# HDR_camera_controller.net
KiCad netlist of a schematic drawn in EAGLE
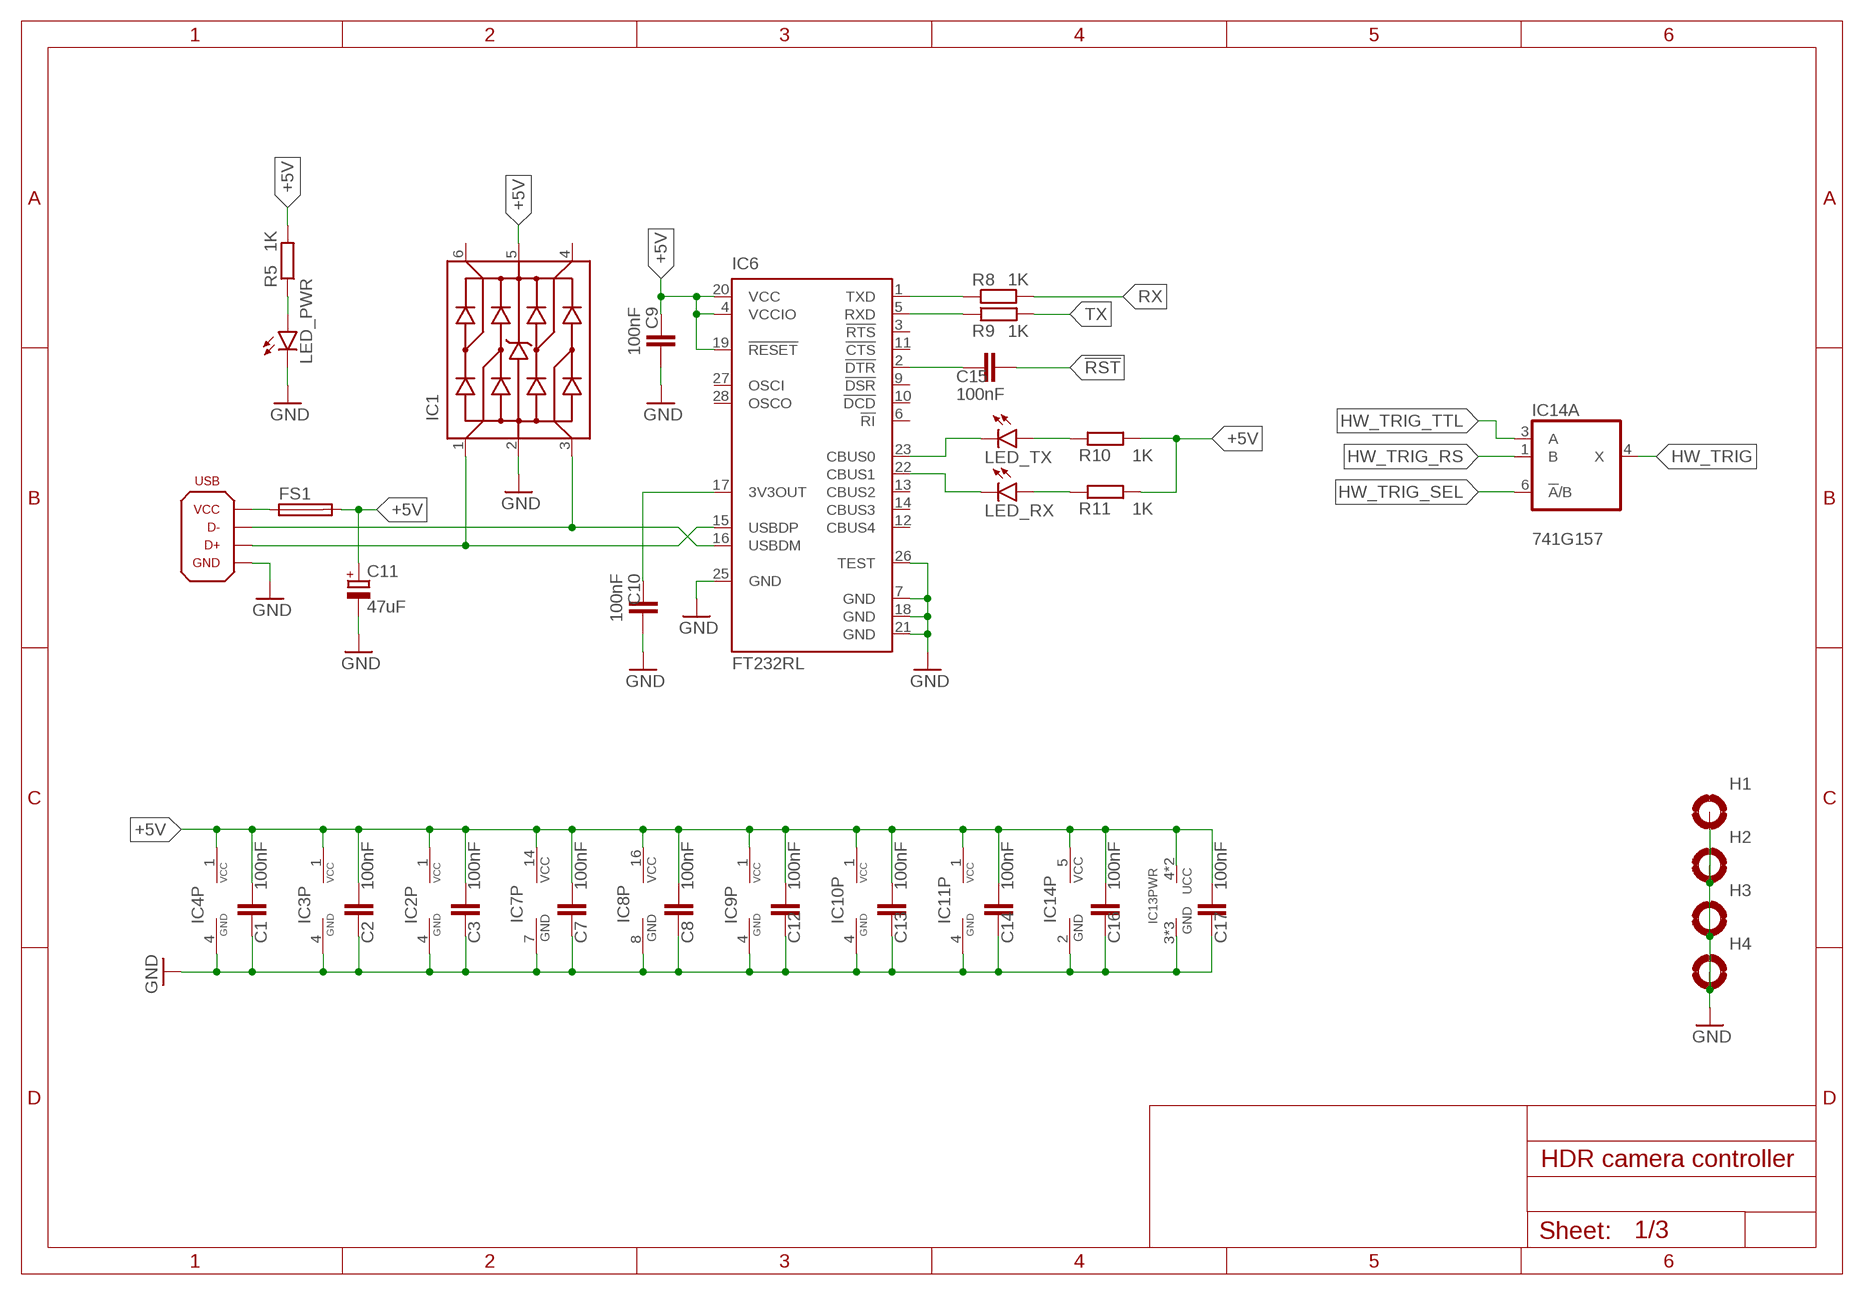
[diagram p0: schematic, sheet 1]
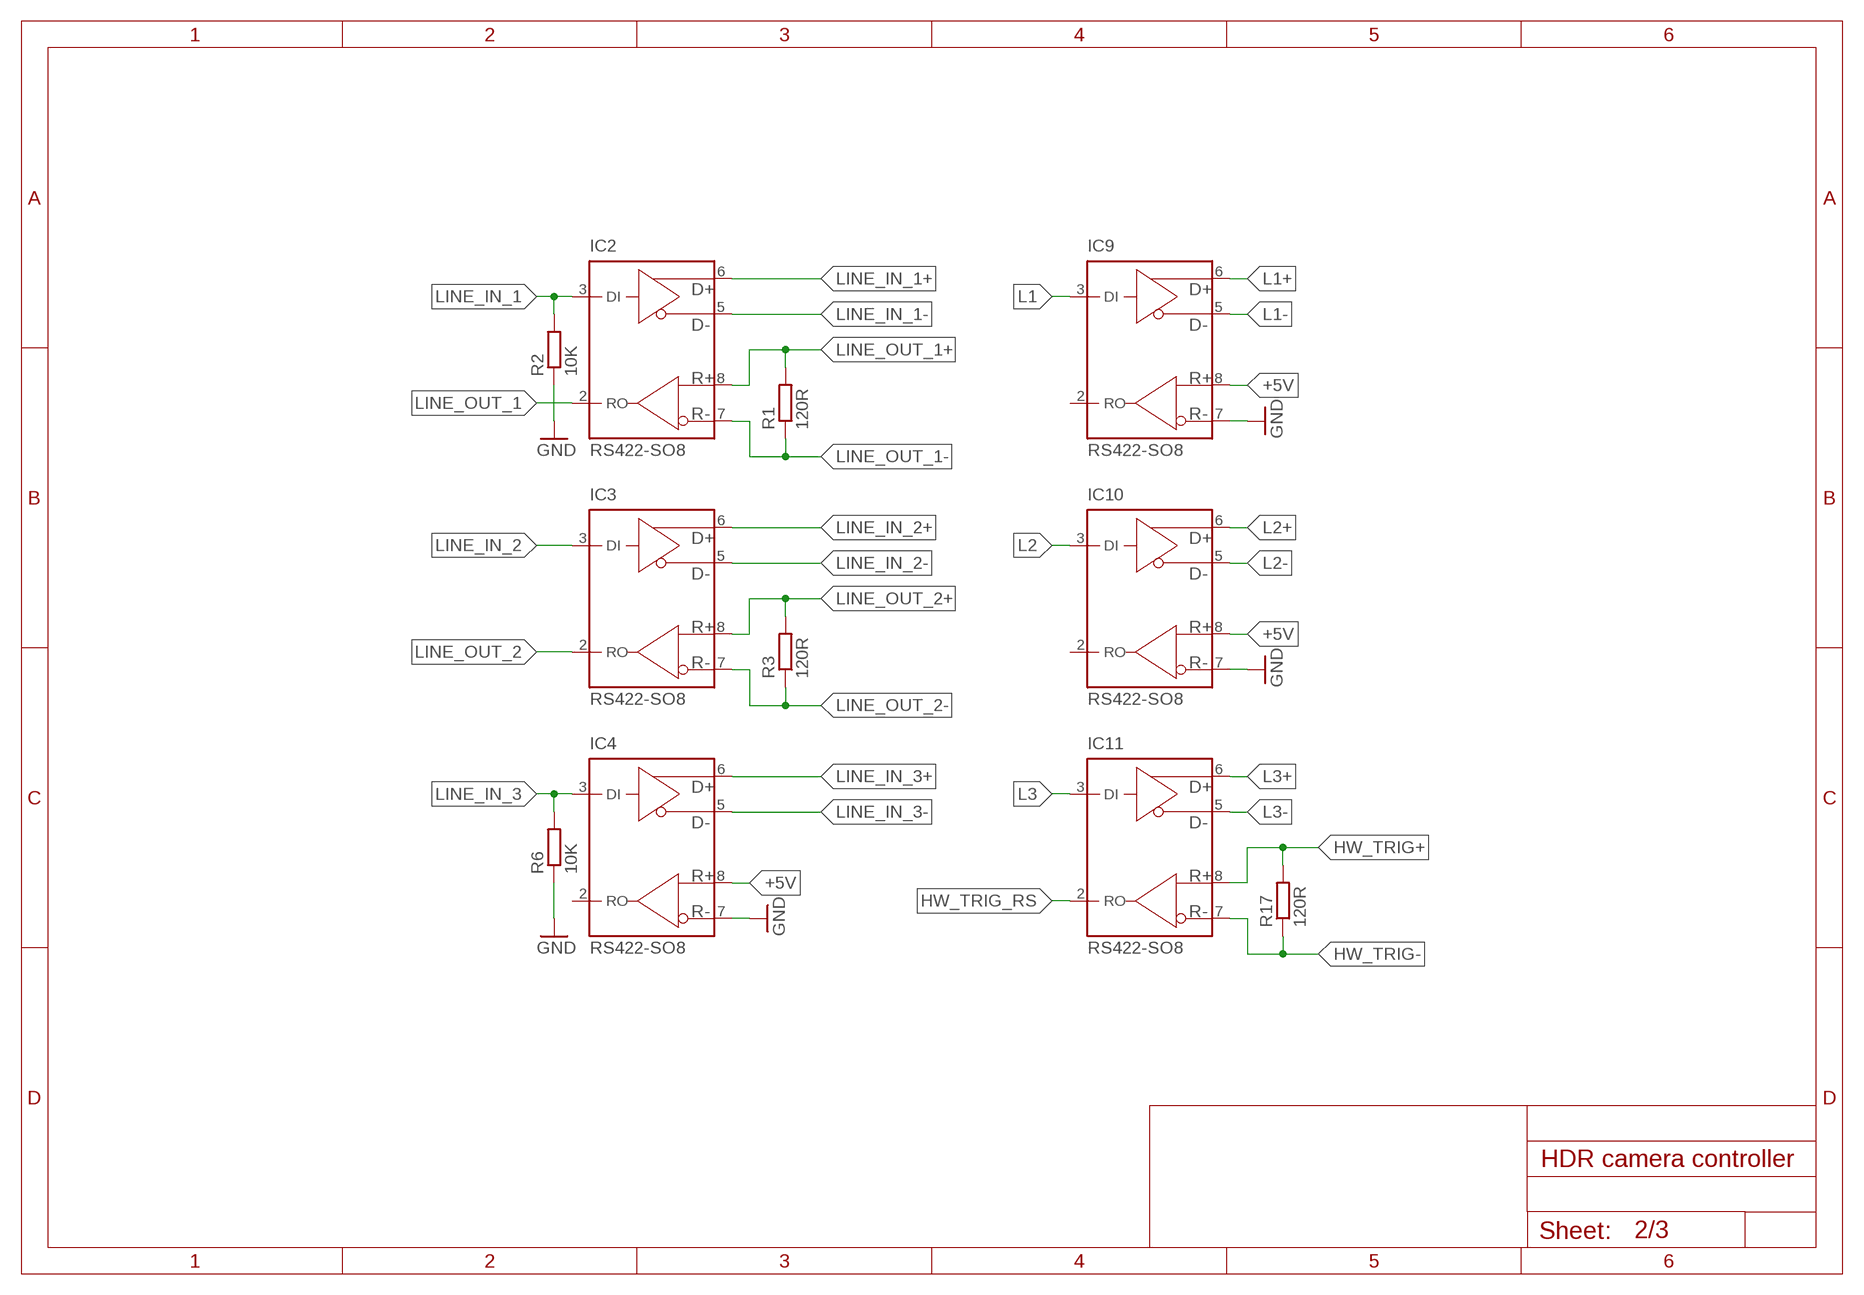
[diagram p1: schematic, sheet 2]
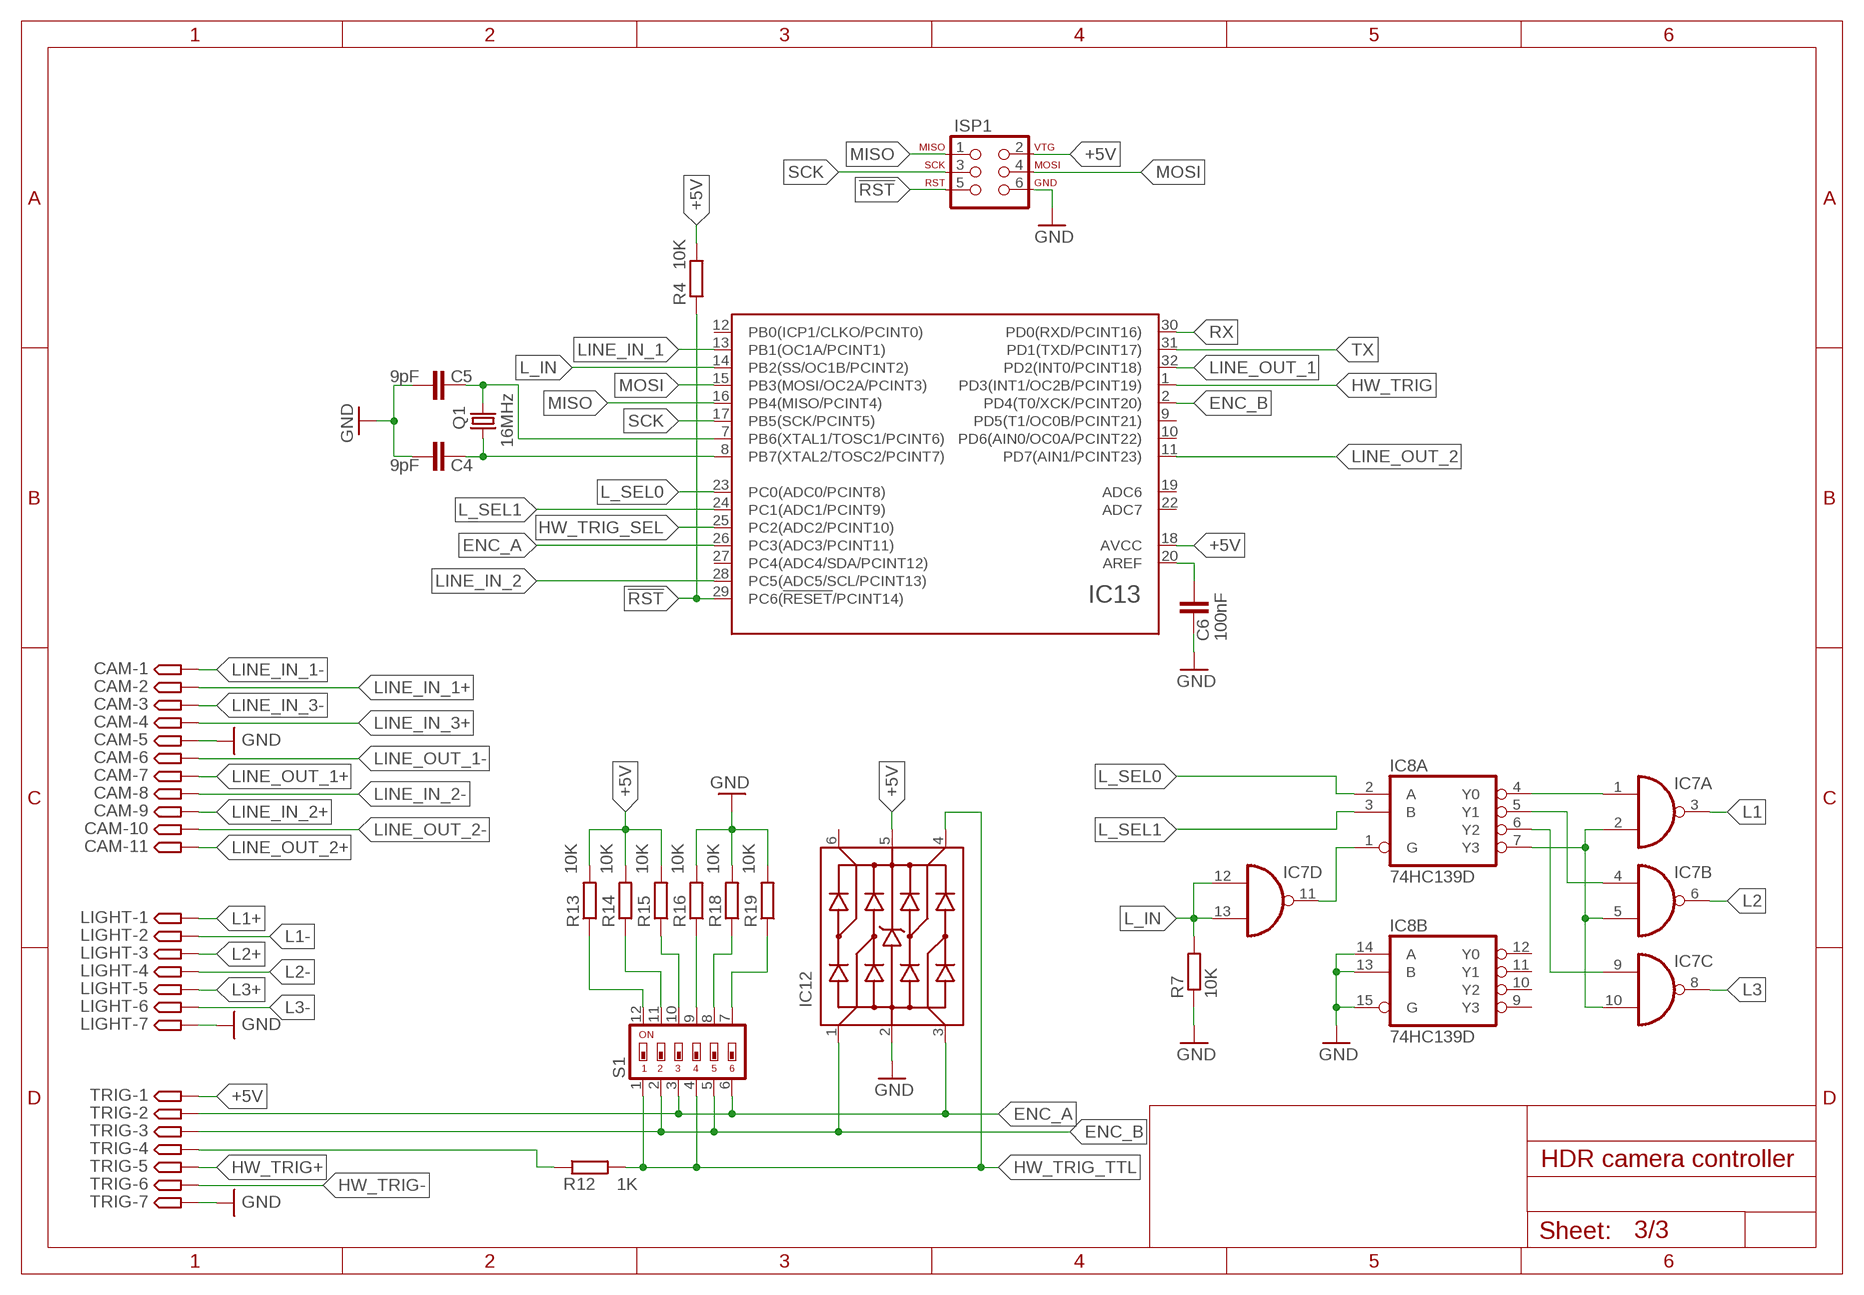
[diagram p2: schematic, sheet 3]

(export (version "E")
  (design (tool "Eeschema 10.0.6"))
  (components
    (comp (ref "C1")
      (value "100nF")
      (footprint "eagle-import:C0805")
      (libsource (lib "eagle-import") (part "C-EUC0805"))
    )
    (comp (ref "C2")
      (value "100nF")
      (footprint "eagle-import:C0805")
      (libsource (lib "eagle-import") (part "C-EUC0805"))
    )
    (comp (ref "C3")
      (value "100nF")
      (footprint "eagle-import:C0805")
      (libsource (lib "eagle-import") (part "C-EUC0805"))
    )
    (comp (ref "C7")
      (value "100nF")
      (footprint "eagle-import:C0805")
      (libsource (lib "eagle-import") (part "C-EUC0805"))
    )
    (comp (ref "C8")
      (value "100nF")
      (footprint "eagle-import:C0805")
      (libsource (lib "eagle-import") (part "C-EUC0805"))
    )
    (comp (ref "C9")
      (value "100nF")
      (footprint "eagle-import:C0805")
      (libsource (lib "eagle-import") (part "C-EUC0805"))
    )
    (comp (ref "C10")
      (value "100nF")
      (footprint "eagle-import:C0805")
      (libsource (lib "eagle-import") (part "C-EUC0805"))
    )
    (comp (ref "C11")
      (value "47uF")
      (footprint "eagle-import:153CLV-0605")
      (fields (field (name "MPN") "SC1E476M6L005VR"))
      (libsource (lib "eagle-import") (part "CPOL-EU153CLV-0605"))
    )
    (comp (ref "C12")
      (value "100nF")
      (footprint "eagle-import:C0805")
      (libsource (lib "eagle-import") (part "C-EUC0805"))
    )
    (comp (ref "C13")
      (value "100nF")
      (footprint "eagle-import:C0805")
      (libsource (lib "eagle-import") (part "C-EUC0805"))
    )
    (comp (ref "C14")
      (value "100nF")
      (footprint "eagle-import:C0805")
      (libsource (lib "eagle-import") (part "C-EUC0805"))
    )
    (comp (ref "C15")
      (value "100nF")
      (footprint "eagle-import:C0805")
      (libsource (lib "eagle-import") (part "C-EUC0805"))
    )
    (comp (ref "C16")
      (value "100nF")
      (footprint "eagle-import:C0805")
      (libsource (lib "eagle-import") (part "C-EUC0805"))
    )
    (comp (ref "C17")
      (value "100nF")
      (footprint "eagle-import:C0805")
      (libsource (lib "eagle-import") (part "C-EUC0805"))
    )
    (comp (ref "FS1")
      (value "POLYFUSE_1210")
      (footprint "eagle-import:1210")
      (fields (field (name "MPN") "SM010-60"))
      (libsource (lib "eagle-import") (part "POLYFUSE_1210"))
    )
    (comp (ref "H1")
      (value "HOLE-3MM_PLATED")
      (footprint "eagle-import:3MM_PLATED")
      (libsource (lib "eagle-import") (part "HOLE-3MM_PLATED"))
    )
    (comp (ref "H2")
      (value "HOLE-3MM_PLATED")
      (footprint "eagle-import:3MM_PLATED")
      (libsource (lib "eagle-import") (part "HOLE-3MM_PLATED"))
    )
    (comp (ref "H3")
      (value "HOLE-3MM_PLATED")
      (footprint "eagle-import:3MM_PLATED")
      (libsource (lib "eagle-import") (part "HOLE-3MM_PLATED"))
    )
    (comp (ref "H4")
      (value "HOLE-3MM_PLATED")
      (footprint "eagle-import:3MM_PLATED")
      (libsource (lib "eagle-import") (part "HOLE-3MM_PLATED"))
    )
    (comp (ref "IC1")
      (value "USBLC6-4")
      (footprint "eagle-import:SOT23-6")
      (fields (field (name "MPN") "USBLC6"))
      (libsource (lib "eagle-import") (part "USBLC6-4"))
    )
    (comp (ref "IC2")
      (value "RS422-SO8")
      (footprint "eagle-import:SO08")
      (fields
        (field (name "MF") "MAXIM")
        (field (name "MPN") "MAX488CSA")
        (field (name "MPN_1") "DS8921AMX/NOPB")
      )
      (libsource (lib "eagle-import") (part "RS422-SO8"))
    )
    (comp (ref "IC3")
      (value "RS422-SO8")
      (footprint "eagle-import:SO08")
      (fields
        (field (name "MF") "MAXIM")
        (field (name "MPN") "MAX488CSA")
        (field (name "MPN_1") "DS8921AMX/NOPB")
      )
      (libsource (lib "eagle-import") (part "RS422-SO8"))
    )
    (comp (ref "IC4")
      (value "RS422-SO8")
      (footprint "eagle-import:SO08")
      (fields
        (field (name "MF") "MAXIM")
        (field (name "MPN") "MAX488CSA")
        (field (name "MPN_1") "DS8921AMX/NOPB")
      )
      (libsource (lib "eagle-import") (part "RS422-SO8"))
    )
    (comp (ref "IC6")
      (value "FT232RL")
      (footprint "eagle-import:SSOP28")
      (libsource (lib "eagle-import") (part "FT232RL"))
    )
    (comp (ref "IC7")
      (value "74HC00D")
      (footprint "eagle-import:SO14")
      (fields (field (name "MPN") "SN74HC00DR"))
      (libsource (lib "eagle-import") (part "7400DHC"))
    )
    (comp (ref "IC8")
      (value "74HC139D")
      (footprint "eagle-import:SO16")
      (fields (field (name "MPN") "SN74HC139DR"))
      (libsource (lib "eagle-import") (part "74139DHC"))
    )
    (comp (ref "IC9")
      (value "RS422-SO8")
      (footprint "eagle-import:SO08")
      (fields
        (field (name "MF") "MAXIM")
        (field (name "MPN") "MAX488CSA")
        (field (name "MPN_1") "DS8921AMX/NOPB")
      )
      (libsource (lib "eagle-import") (part "RS422-SO8"))
    )
    (comp (ref "IC10")
      (value "RS422-SO8")
      (footprint "eagle-import:SO08")
      (fields
        (field (name "MF") "MAXIM")
        (field (name "MPN") "MAX488CSA")
        (field (name "MPN_1") "DS8921AMX/NOPB")
      )
      (libsource (lib "eagle-import") (part "RS422-SO8"))
    )
    (comp (ref "IC11")
      (value "RS422-SO8")
      (footprint "eagle-import:SO08")
      (fields
        (field (name "MF") "MAXIM")
        (field (name "MPN") "MAX488CSA")
        (field (name "MPN_1") "DS8921AMX/NOPB")
      )
      (libsource (lib "eagle-import") (part "RS422-SO8"))
    )
    (comp (ref "IC13")
      (value "ATMEGA48/88/168/328-AU")
      (footprint "eagle-import:TQFP32-08")
      (libsource (lib "eagle-import") (part "ATMEGA48/88/168/328-AU"))
    )
    (comp (ref "IC14")
      (value "741G157")
      (footprint "eagle-import:SOT457W_PHILIPS")
      (fields (field (name "MPN") "74LVC1G157GV.125"))
      (libsource (lib "eagle-import") (part "741G157"))
    )
    (comp (ref "LED_PWR")
      (value "LEDSML0805")
      (footprint "eagle-import:SML0805")
      (libsource (lib "eagle-import") (part "LEDSML0805"))
    )
    (comp (ref "LED_RX")
      (value "LEDSML0805")
      (footprint "eagle-import:SML0805")
      (libsource (lib "eagle-import") (part "LEDSML0805"))
    )
    (comp (ref "LED_TX")
      (value "LEDSML0805")
      (footprint "eagle-import:SML0805")
      (libsource (lib "eagle-import") (part "LEDSML0805"))
    )
    (comp (ref "R5")
      (value "1K")
      (footprint "eagle-import:R0805")
      (libsource (lib "eagle-import") (part "R-EU_R0805"))
    )
    (comp (ref "R8")
      (value "1K")
      (footprint "eagle-import:R0805")
      (libsource (lib "eagle-import") (part "R-EU_R0805"))
    )
    (comp (ref "R9")
      (value "1K")
      (footprint "eagle-import:R0805")
      (libsource (lib "eagle-import") (part "R-EU_R0805"))
    )
    (comp (ref "R10")
      (value "1K")
      (footprint "eagle-import:R0805")
      (libsource (lib "eagle-import") (part "R-EU_R0805"))
    )
    (comp (ref "R11")
      (value "1K")
      (footprint "eagle-import:R0805")
      (libsource (lib "eagle-import") (part "R-EU_R0805"))
    )
    (comp (ref "USB")
      (value "USB_AB-B_SMD")
      (footprint "eagle-import:USB_B_SMD")
      (fields (field (name "MPN") "USBB-G-SMD"))
      (libsource (lib "eagle-import") (part "USB_AB-B_SMD"))
    )
    (comp (ref "C4")
      (value "9pF")
      (footprint "eagle-import:C0805")
      (libsource (lib "eagle-import") (part "C-EUC0805"))
    )
    (comp (ref "C5")
      (value "9pF")
      (footprint "eagle-import:C0805")
      (libsource (lib "eagle-import") (part "C-EUC0805"))
    )
    (comp (ref "C6")
      (value "100nF")
      (footprint "eagle-import:C0805")
      (libsource (lib "eagle-import") (part "C-EUC0805"))
    )
    (comp (ref "CAM")
      (value "SMPAD-11")
      (footprint "eagle-import:S-11P")
      (libsource (lib "eagle-import") (part "SMPAD-11"))
    )
    (comp (ref "IC12")
      (value "USBLC6-4")
      (footprint "eagle-import:SOT23-6")
      (fields (field (name "MPN") "USBLC6"))
      (libsource (lib "eagle-import") (part "USBLC6-4"))
    )
    (comp (ref "ISP1")
      (value "ISP-SMD")
      (footprint "eagle-import:ISP_SMD")
      (libsource (lib "eagle-import") (part "ISP-SMD"))
    )
    (comp (ref "LIGHT")
      (value "SMPAD-7")
      (footprint "eagle-import:S-7P")
      (libsource (lib "eagle-import") (part "SMPAD-7"))
    )
    (comp (ref "Q1")
      (value "16MHz")
      (footprint "eagle-import:CRYSTAL-3.2X2.5")
      (fields (field (name "MPN") "3225-16M-SR"))
      (libsource (lib "eagle-import") (part "RESONATOR_CRY"))
    )
    (comp (ref "R4")
      (value "10K")
      (footprint "eagle-import:R0805")
      (libsource (lib "eagle-import") (part "R-EU_R0805"))
    )
    (comp (ref "R7")
      (value "10K")
      (footprint "eagle-import:R0805")
      (libsource (lib "eagle-import") (part "R-EU_R0805"))
    )
    (comp (ref "R12")
      (value "1K")
      (footprint "eagle-import:R0805")
      (libsource (lib "eagle-import") (part "R-EU_R0805"))
    )
    (comp (ref "R13")
      (value "10K")
      (footprint "eagle-import:R0805")
      (libsource (lib "eagle-import") (part "R-EU_R0805"))
    )
    (comp (ref "R14")
      (value "10K")
      (footprint "eagle-import:R0805")
      (libsource (lib "eagle-import") (part "R-EU_R0805"))
    )
    (comp (ref "R15")
      (value "10K")
      (footprint "eagle-import:R0805")
      (libsource (lib "eagle-import") (part "R-EU_R0805"))
    )
    (comp (ref "R16")
      (value "10K")
      (footprint "eagle-import:R0805")
      (libsource (lib "eagle-import") (part "R-EU_R0805"))
    )
    (comp (ref "R18")
      (value "10K")
      (footprint "eagle-import:R0805")
      (libsource (lib "eagle-import") (part "R-EU_R0805"))
    )
    (comp (ref "R19")
      (value "10K")
      (footprint "eagle-import:R0805")
      (libsource (lib "eagle-import") (part "R-EU_R0805"))
    )
    (comp (ref "S1")
      (value "SWS006")
      (footprint "eagle-import:SMS-006")
      (fields (field (name "MPN") "A6S-6102-H"))
      (libsource (lib "eagle-import") (part "SWS006"))
    )
    (comp (ref "TRIG")
      (value "SMPAD-7")
      (footprint "eagle-import:S-7P")
      (libsource (lib "eagle-import") (part "SMPAD-7"))
    )
    (comp (ref "R1")
      (value "120R")
      (footprint "eagle-import:R0805")
      (libsource (lib "eagle-import") (part "R-EU_R0805"))
    )
    (comp (ref "R2")
      (value "10K")
      (footprint "eagle-import:R0805")
      (libsource (lib "eagle-import") (part "R-EU_R0805"))
    )
    (comp (ref "R3")
      (value "120R")
      (footprint "eagle-import:R0805")
      (libsource (lib "eagle-import") (part "R-EU_R0805"))
    )
    (comp (ref "R6")
      (value "10K")
      (footprint "eagle-import:R0805")
      (libsource (lib "eagle-import") (part "R-EU_R0805"))
    )
    (comp (ref "R17")
      (value "120R")
      (footprint "eagle-import:R0805")
      (libsource (lib "eagle-import") (part "R-EU_R0805"))
    )
  )
  (nets
    (net (code "1") (name "+5V") (class "Default")
      (node (ref "C1") (pin "1") (pinfunction "1_1") (pintype "passive"))
      (node (ref "C11") (pin "+") (pinfunction "+_+") (pintype "passive"))
      (node (ref "C12") (pin "1") (pinfunction "1_1") (pintype "passive"))
      (node (ref "C13") (pin "1") (pinfunction "1_1") (pintype "passive"))
      (node (ref "C14") (pin "1") (pinfunction "1_1") (pintype "passive"))
      (node (ref "C16") (pin "1") (pinfunction "1_1") (pintype "passive"))
      (node (ref "C17") (pin "1") (pinfunction "1_1") (pintype "passive"))
      (node (ref "C2") (pin "1") (pinfunction "1_1") (pintype "passive"))
      (node (ref "C3") (pin "1") (pinfunction "1_1") (pintype "passive"))
      (node (ref "C7") (pin "1") (pinfunction "1_1") (pintype "passive"))
      (node (ref "C8") (pin "1") (pinfunction "1_1") (pintype "passive"))
      (node (ref "C9") (pin "2") (pinfunction "2_2") (pintype "passive"))
      (node (ref "FS1") (pin "2") (pinfunction "2_2") (pintype "passive"))
      (node (ref "IC1") (pin "5") (pinfunction "P$5_5") (pintype "bidirectional"))
      (node (ref "IC10") (pin "1") (pinfunction "VCC_1") (pintype "power_in"))
      (node (ref "IC10") (pin "8") (pinfunction "R+_8") (pintype "input"))
      (node (ref "IC11") (pin "1") (pinfunction "VCC_1") (pintype "power_in"))
      (node (ref "IC12") (pin "5") (pinfunction "P$5_5") (pintype "bidirectional"))
      (node (ref "IC13") (pin "18") (pinfunction "AVCC_18") (pintype "power_in"))
      (node (ref "IC13") (pin "4") (pinfunction "UCC_4") (pintype "power_in"))
      (node (ref "IC13") (pin "6") (pinfunction "UCC_6") (pintype "power_in"))
      (node (ref "IC14") (pin "5") (pinfunction "VCC_5") (pintype "power_in"))
      (node (ref "IC2") (pin "1") (pinfunction "VCC_1") (pintype "power_in"))
      (node (ref "IC3") (pin "1") (pinfunction "VCC_1") (pintype "power_in"))
      (node (ref "IC4") (pin "1") (pinfunction "VCC_1") (pintype "power_in"))
      (node (ref "IC4") (pin "8") (pinfunction "R+_8") (pintype "input"))
      (node (ref "IC6") (pin "19") (pinfunction "~{RESET}_19") (pintype "input"))
      (node (ref "IC6") (pin "20") (pinfunction "VCC_20") (pintype "power_in"))
      (node (ref "IC6") (pin "4") (pinfunction "VCCIO_4") (pintype "power_in"))
      (node (ref "IC7") (pin "14") (pinfunction "VCC_14") (pintype "power_in"))
      (node (ref "IC8") (pin "16") (pinfunction "VCC_16") (pintype "power_in"))
      (node (ref "IC9") (pin "1") (pinfunction "VCC_1") (pintype "power_in"))
      (node (ref "IC9") (pin "8") (pinfunction "R+_8") (pintype "input"))
      (node (ref "ISP1") (pin "2") (pinfunction "VTG_2") (pintype "passive"))
      (node (ref "R10") (pin "2") (pinfunction "2_2") (pintype "passive"))
      (node (ref "R11") (pin "2") (pinfunction "2_2") (pintype "passive"))
      (node (ref "R13") (pin "2") (pinfunction "2_2") (pintype "passive"))
      (node (ref "R14") (pin "2") (pinfunction "2_2") (pintype "passive"))
      (node (ref "R15") (pin "2") (pinfunction "2_2") (pintype "passive"))
      (node (ref "R4") (pin "2") (pinfunction "2_2") (pintype "passive"))
      (node (ref "R5") (pin "2") (pinfunction "2_2") (pintype "passive"))
      (node (ref "TRIG") (pin "1") (pinfunction "P_1") (pintype "passive"))
    )
    (net (code "2") (name "ENC_A") (class "Default")
      (node (ref "IC12") (pin "3") (pinfunction "P$3_3") (pintype "bidirectional"))
      (node (ref "IC13") (pin "26") (pinfunction "PC3(ADC3/PCINT11)_26") (pintype "bidirectional"))
      (node (ref "S1") (pin "3") (pinfunction "3_3") (pintype "passive"))
      (node (ref "S1") (pin "6") (pinfunction "6_6") (pintype "passive"))
      (node (ref "TRIG") (pin "2") (pinfunction "P_2") (pintype "passive"))
    )
    (net (code "3") (name "ENC_B") (class "Default")
      (node (ref "IC12") (pin "1") (pinfunction "P$1_1") (pintype "bidirectional"))
      (node (ref "IC13") (pin "2") (pinfunction "PD4(T0/XCK/PCINT20)_2") (pintype "bidirectional"))
      (node (ref "S1") (pin "2") (pinfunction "2_2") (pintype "passive"))
      (node (ref "S1") (pin "5") (pinfunction "5_5") (pintype "passive"))
      (node (ref "TRIG") (pin "3") (pinfunction "P_3") (pintype "passive"))
    )
    (net (code "4") (name "GND") (class "Default")
      (node (ref "C1") (pin "2") (pinfunction "2_2") (pintype "passive"))
      (node (ref "C10") (pin "1") (pinfunction "1_1") (pintype "passive"))
      (node (ref "C11") (pin "-") (pinfunction "-_-") (pintype "passive"))
      (node (ref "C12") (pin "2") (pinfunction "2_2") (pintype "passive"))
      (node (ref "C13") (pin "2") (pinfunction "2_2") (pintype "passive"))
      (node (ref "C14") (pin "2") (pinfunction "2_2") (pintype "passive"))
      (node (ref "C16") (pin "2") (pinfunction "2_2") (pintype "passive"))
      (node (ref "C17") (pin "2") (pinfunction "2_2") (pintype "passive"))
      (node (ref "C2") (pin "2") (pinfunction "2_2") (pintype "passive"))
      (node (ref "C3") (pin "2") (pinfunction "2_2") (pintype "passive"))
      (node (ref "C4") (pin "1") (pinfunction "1_1") (pintype "passive"))
      (node (ref "C5") (pin "1") (pinfunction "1_1") (pintype "passive"))
      (node (ref "C6") (pin "2") (pinfunction "2_2") (pintype "passive"))
      (node (ref "C7") (pin "2") (pinfunction "2_2") (pintype "passive"))
      (node (ref "C8") (pin "2") (pinfunction "2_2") (pintype "passive"))
      (node (ref "C9") (pin "1") (pinfunction "1_1") (pintype "passive"))
      (node (ref "CAM") (pin "5") (pinfunction "P_5") (pintype "passive"))
      (node (ref "H1") (pin "1") (pinfunction "MOUNT_1") (pintype "passive"))
      (node (ref "H2") (pin "1") (pinfunction "MOUNT_1") (pintype "passive"))
      (node (ref "H3") (pin "1") (pinfunction "MOUNT_1") (pintype "passive"))
      (node (ref "H4") (pin "1") (pinfunction "MOUNT_1") (pintype "passive"))
      (node (ref "IC1") (pin "2") (pinfunction "P$2_2") (pintype "bidirectional"))
      (node (ref "IC10") (pin "4") (pinfunction "GND_4") (pintype "power_in"))
      (node (ref "IC10") (pin "7") (pinfunction "R-_7") (pintype "input"))
      (node (ref "IC11") (pin "4") (pinfunction "GND_4") (pintype "power_in"))
      (node (ref "IC12") (pin "2") (pinfunction "P$2_2") (pintype "bidirectional"))
      (node (ref "IC13") (pin "21") (pinfunction "GND_21") (pintype "power_in"))
      (node (ref "IC13") (pin "3") (pinfunction "GND_3") (pintype "power_in"))
      (node (ref "IC13") (pin "5") (pinfunction "GND_5") (pintype "power_in"))
      (node (ref "IC14") (pin "2") (pinfunction "GND_2") (pintype "power_in"))
      (node (ref "IC2") (pin "4") (pinfunction "GND_4") (pintype "power_in"))
      (node (ref "IC3") (pin "4") (pinfunction "GND_4") (pintype "power_in"))
      (node (ref "IC4") (pin "4") (pinfunction "GND_4") (pintype "power_in"))
      (node (ref "IC4") (pin "7") (pinfunction "R-_7") (pintype "input"))
      (node (ref "IC6") (pin "18") (pinfunction "GND_18") (pintype "power_in"))
      (node (ref "IC6") (pin "21") (pinfunction "GND_21") (pintype "power_in"))
      (node (ref "IC6") (pin "25") (pinfunction "GND_25") (pintype "power_in"))
      (node (ref "IC6") (pin "26") (pinfunction "TEST_26") (pintype "input"))
      (node (ref "IC6") (pin "7") (pinfunction "GND_7") (pintype "power_in"))
      (node (ref "IC7") (pin "7") (pinfunction "GND_7") (pintype "power_in"))
      (node (ref "IC8") (pin "13") (pinfunction "B_13") (pintype "input"))
      (node (ref "IC8") (pin "14") (pinfunction "A_14") (pintype "input"))
      (node (ref "IC8") (pin "15") (pinfunction "G_15") (pintype "input"))
      (node (ref "IC8") (pin "8") (pinfunction "GND_8") (pintype "power_in"))
      (node (ref "IC9") (pin "4") (pinfunction "GND_4") (pintype "power_in"))
      (node (ref "IC9") (pin "7") (pinfunction "R-_7") (pintype "input"))
      (node (ref "ISP1") (pin "6") (pinfunction "GND_6") (pintype "passive"))
      (node (ref "LED_PWR") (pin "C") (pinfunction "C_C") (pintype "passive"))
      (node (ref "LIGHT") (pin "7") (pinfunction "P_7") (pintype "passive"))
      (node (ref "R16") (pin "2") (pinfunction "2_2") (pintype "passive"))
      (node (ref "R18") (pin "2") (pinfunction "2_2") (pintype "passive"))
      (node (ref "R19") (pin "2") (pinfunction "2_2") (pintype "passive"))
      (node (ref "R2") (pin "1") (pinfunction "1_1") (pintype "passive"))
      (node (ref "R6") (pin "1") (pinfunction "1_1") (pintype "passive"))
      (node (ref "R7") (pin "1") (pinfunction "1_1") (pintype "passive"))
      (node (ref "TRIG") (pin "7") (pinfunction "P_7") (pintype "passive"))
      (node (ref "USB") (pin "4") (pinfunction "GND_4") (pintype "bidirectional"))
      (node (ref "USB") (pin "G1") (pinfunction "GND_G1") (pintype "bidirectional"))
      (node (ref "USB") (pin "G2") (pinfunction "GND_G2") (pintype "bidirectional"))
    )
    (net (code "5") (name "HW_TRIG") (class "Default")
      (node (ref "IC13") (pin "1") (pinfunction "PD3(INT1/OC2B/PCINT19)_1") (pintype "bidirectional"))
      (node (ref "IC14") (pin "4") (pinfunction "X_4") (pintype "bidirectional"))
    )
    (net (code "6") (name "HW_TRIG+") (class "Default")
      (node (ref "IC11") (pin "8") (pinfunction "R+_8") (pintype "input"))
      (node (ref "R17") (pin "2") (pinfunction "2_2") (pintype "passive"))
      (node (ref "TRIG") (pin "5") (pinfunction "P_5") (pintype "passive"))
    )
    (net (code "7") (name "HW_TRIG-") (class "Default")
      (node (ref "IC11") (pin "7") (pinfunction "R-_7") (pintype "input"))
      (node (ref "R17") (pin "1") (pinfunction "1_1") (pintype "passive"))
      (node (ref "TRIG") (pin "6") (pinfunction "P_6") (pintype "passive"))
    )
    (net (code "8") (name "HW_TRIG_RS") (class "Default")
      (node (ref "IC11") (pin "2") (pinfunction "RO_2") (pintype "output"))
      (node (ref "IC14") (pin "1") (pinfunction "B_1") (pintype "bidirectional"))
    )
    (net (code "9") (name "HW_TRIG_SEL") (class "Default")
      (node (ref "IC13") (pin "25") (pinfunction "PC2(ADC2/PCINT10)_25") (pintype "bidirectional"))
      (node (ref "IC14") (pin "6") (pinfunction "~{A}/B_6") (pintype "input"))
    )
    (net (code "10") (name "HW_TRIG_TTL") (class "Default")
      (node (ref "IC12") (pin "4") (pinfunction "P$4_4") (pintype "bidirectional"))
      (node (ref "IC14") (pin "3") (pinfunction "A_3") (pintype "bidirectional"))
      (node (ref "R12") (pin "2") (pinfunction "2_2") (pintype "passive"))
      (node (ref "S1") (pin "1") (pinfunction "1_1") (pintype "passive"))
      (node (ref "S1") (pin "4") (pinfunction "4_4") (pintype "passive"))
    )
    (net (code "11") (name "L1") (class "Default")
      (node (ref "IC7") (pin "3") (pinfunction "O_3") (pintype "output"))
      (node (ref "IC9") (pin "3") (pinfunction "DI_3") (pintype "input"))
    )
    (net (code "12") (name "L1+") (class "Default")
      (node (ref "IC9") (pin "6") (pinfunction "D+_6") (pintype "output"))
      (node (ref "LIGHT") (pin "1") (pinfunction "P_1") (pintype "passive"))
    )
    (net (code "13") (name "L1-") (class "Default")
      (node (ref "IC9") (pin "5") (pinfunction "D-_5") (pintype "output"))
      (node (ref "LIGHT") (pin "2") (pinfunction "P_2") (pintype "passive"))
    )
    (net (code "14") (name "L2") (class "Default")
      (node (ref "IC10") (pin "3") (pinfunction "DI_3") (pintype "input"))
      (node (ref "IC7") (pin "6") (pinfunction "O_6") (pintype "output"))
    )
    (net (code "15") (name "L2+") (class "Default")
      (node (ref "IC10") (pin "6") (pinfunction "D+_6") (pintype "output"))
      (node (ref "LIGHT") (pin "3") (pinfunction "P_3") (pintype "passive"))
    )
    (net (code "16") (name "L2-") (class "Default")
      (node (ref "IC10") (pin "5") (pinfunction "D-_5") (pintype "output"))
      (node (ref "LIGHT") (pin "4") (pinfunction "P_4") (pintype "passive"))
    )
    (net (code "17") (name "L3") (class "Default")
      (node (ref "IC11") (pin "3") (pinfunction "DI_3") (pintype "input"))
      (node (ref "IC7") (pin "8") (pinfunction "O_8") (pintype "output"))
    )
    (net (code "18") (name "L3+") (class "Default")
      (node (ref "IC11") (pin "6") (pinfunction "D+_6") (pintype "output"))
      (node (ref "LIGHT") (pin "5") (pinfunction "P_5") (pintype "passive"))
    )
    (net (code "19") (name "L3-") (class "Default")
      (node (ref "IC11") (pin "5") (pinfunction "D-_5") (pintype "output"))
      (node (ref "LIGHT") (pin "6") (pinfunction "P_6") (pintype "passive"))
    )
    (net (code "20") (name "LINE_IN_1") (class "Default")
      (node (ref "IC13") (pin "13") (pinfunction "PB1(OC1A/PCINT1)_13") (pintype "bidirectional"))
      (node (ref "IC2") (pin "3") (pinfunction "DI_3") (pintype "input"))
      (node (ref "R2") (pin "2") (pinfunction "2_2") (pintype "passive"))
    )
    (net (code "21") (name "LINE_IN_1+") (class "Default")
      (node (ref "CAM") (pin "2") (pinfunction "P_2") (pintype "passive"))
      (node (ref "IC2") (pin "6") (pinfunction "D+_6") (pintype "output"))
    )
    (net (code "22") (name "LINE_IN_1-") (class "Default")
      (node (ref "CAM") (pin "1") (pinfunction "P_1") (pintype "passive"))
      (node (ref "IC2") (pin "5") (pinfunction "D-_5") (pintype "output"))
    )
    (net (code "23") (name "LINE_IN_2") (class "Default")
      (node (ref "IC13") (pin "28") (pinfunction "PC5(ADC5/SCL/PCINT13)_28") (pintype "bidirectional"))
      (node (ref "IC3") (pin "3") (pinfunction "DI_3") (pintype "input"))
    )
    (net (code "24") (name "LINE_IN_2+") (class "Default")
      (node (ref "CAM") (pin "9") (pinfunction "P_9") (pintype "passive"))
      (node (ref "IC3") (pin "6") (pinfunction "D+_6") (pintype "output"))
    )
    (net (code "25") (name "LINE_IN_2-") (class "Default")
      (node (ref "CAM") (pin "8") (pinfunction "P_8") (pintype "passive"))
      (node (ref "IC3") (pin "5") (pinfunction "D-_5") (pintype "output"))
    )
    (net (code "26") (name "LINE_IN_3") (class "Default")
      (node (ref "IC4") (pin "3") (pinfunction "DI_3") (pintype "input"))
      (node (ref "R6") (pin "2") (pinfunction "2_2") (pintype "passive"))
    )
    (net (code "27") (name "LINE_IN_3+") (class "Default")
      (node (ref "CAM") (pin "4") (pinfunction "P_4") (pintype "passive"))
      (node (ref "IC4") (pin "6") (pinfunction "D+_6") (pintype "output"))
    )
    (net (code "28") (name "LINE_IN_3-") (class "Default")
      (node (ref "CAM") (pin "3") (pinfunction "P_3") (pintype "passive"))
      (node (ref "IC4") (pin "5") (pinfunction "D-_5") (pintype "output"))
    )
    (net (code "29") (name "LINE_OUT_1") (class "Default")
      (node (ref "IC13") (pin "32") (pinfunction "PD2(INT0/PCINT18)_32") (pintype "bidirectional"))
      (node (ref "IC2") (pin "2") (pinfunction "RO_2") (pintype "output"))
    )
    (net (code "30") (name "LINE_OUT_1+") (class "Default")
      (node (ref "CAM") (pin "7") (pinfunction "P_7") (pintype "passive"))
      (node (ref "IC2") (pin "8") (pinfunction "R+_8") (pintype "input"))
      (node (ref "R1") (pin "2") (pinfunction "2_2") (pintype "passive"))
    )
    (net (code "31") (name "LINE_OUT_1-") (class "Default")
      (node (ref "CAM") (pin "6") (pinfunction "P_6") (pintype "passive"))
      (node (ref "IC2") (pin "7") (pinfunction "R-_7") (pintype "input"))
      (node (ref "R1") (pin "1") (pinfunction "1_1") (pintype "passive"))
    )
    (net (code "32") (name "LINE_OUT_2") (class "Default")
      (node (ref "IC13") (pin "11") (pinfunction "PD7(AIN1/PCINT23)_11") (pintype "bidirectional"))
      (node (ref "IC3") (pin "2") (pinfunction "RO_2") (pintype "output"))
    )
    (net (code "33") (name "LINE_OUT_2+") (class "Default")
      (node (ref "CAM") (pin "11") (pinfunction "P_11") (pintype "passive"))
      (node (ref "IC3") (pin "8") (pinfunction "R+_8") (pintype "input"))
      (node (ref "R3") (pin "2") (pinfunction "2_2") (pintype "passive"))
    )
    (net (code "34") (name "LINE_OUT_2-") (class "Default")
      (node (ref "CAM") (pin "10") (pinfunction "P_10") (pintype "passive"))
      (node (ref "IC3") (pin "7") (pinfunction "R-_7") (pintype "input"))
      (node (ref "R3") (pin "1") (pinfunction "1_1") (pintype "passive"))
    )
    (net (code "35") (name "L_IN") (class "Default")
      (node (ref "IC13") (pin "14") (pinfunction "PB2(SS/OC1B/PCINT2)_14") (pintype "bidirectional"))
      (node (ref "IC7") (pin "12") (pinfunction "I0_12") (pintype "input"))
      (node (ref "IC7") (pin "13") (pinfunction "I1_13") (pintype "input"))
      (node (ref "R7") (pin "2") (pinfunction "2_2") (pintype "passive"))
    )
    (net (code "36") (name "L_SEL0") (class "Default")
      (node (ref "IC13") (pin "23") (pinfunction "PC0(ADC0/PCINT8)_23") (pintype "bidirectional"))
      (node (ref "IC8") (pin "2") (pinfunction "A_2") (pintype "input"))
    )
    (net (code "37") (name "L_SEL1") (class "Default")
      (node (ref "IC13") (pin "24") (pinfunction "PC1(ADC1/PCINT9)_24") (pintype "bidirectional"))
      (node (ref "IC8") (pin "3") (pinfunction "B_3") (pintype "input"))
    )
    (net (code "38") (name "MISO") (class "Default")
      (node (ref "IC13") (pin "16") (pinfunction "PB4(MISO/PCINT4)_16") (pintype "bidirectional"))
      (node (ref "ISP1") (pin "1") (pinfunction "MISO_1") (pintype "passive"))
    )
    (net (code "39") (name "MOSI") (class "Default")
      (node (ref "IC13") (pin "15") (pinfunction "PB3(MOSI/OC2A/PCINT3)_15") (pintype "bidirectional"))
      (node (ref "ISP1") (pin "4") (pinfunction "MOSI_4") (pintype "passive"))
    )
    (net (code "40") (name "Net-(IC1-P$1)") (class "Default")
      (node (ref "IC1") (pin "1") (pinfunction "P$1_1") (pintype "bidirectional"))
      (node (ref "IC6") (pin "15") (pinfunction "USBDP_15") (pintype "bidirectional"))
      (node (ref "USB") (pin "3") (pinfunction "D+_3") (pintype "bidirectional"))
    )
    (net (code "41") (name "Net-(IC1-P$3)") (class "Default")
      (node (ref "IC1") (pin "3") (pinfunction "P$3_3") (pintype "bidirectional"))
      (node (ref "IC6") (pin "16") (pinfunction "USBDM_16") (pintype "bidirectional"))
      (node (ref "USB") (pin "2") (pinfunction "D-_2") (pintype "bidirectional"))
    )
    (net (code "42") (name "Net-(IC6-3V3OUT)") (class "Default")
      (node (ref "C10") (pin "2") (pinfunction "2_2") (pintype "passive"))
      (node (ref "IC6") (pin "17") (pinfunction "3V3OUT_17") (pintype "output"))
    )
    (net (code "43") (name "Net-(IC6-CBUS0)") (class "Default")
      (node (ref "IC6") (pin "23") (pinfunction "CBUS0_23") (pintype "bidirectional"))
      (node (ref "LED_TX") (pin "C") (pinfunction "C_C") (pintype "passive"))
    )
    (net (code "44") (name "Net-(IC6-CBUS1)") (class "Default")
      (node (ref "IC6") (pin "22") (pinfunction "CBUS1_22") (pintype "bidirectional"))
      (node (ref "LED_RX") (pin "C") (pinfunction "C_C") (pintype "passive"))
    )
    (net (code "45") (name "Net-(IC6-RXD)") (class "Default")
      (node (ref "IC6") (pin "5") (pinfunction "RXD_5") (pintype "input"))
      (node (ref "R9") (pin "1") (pinfunction "1_1") (pintype "passive"))
    )
    (net (code "46") (name "Net-(IC6-TXD)") (class "Default")
      (node (ref "IC6") (pin "1") (pinfunction "TXD_1") (pintype "output"))
      (node (ref "R8") (pin "1") (pinfunction "1_1") (pintype "passive"))
    )
    (net (code "47") (name "Net-(IC6-~{DTR})") (class "Default")
      (node (ref "C15") (pin "2") (pinfunction "2_2") (pintype "passive"))
      (node (ref "IC6") (pin "2") (pinfunction "~{DTR}_2") (pintype "output"))
    )
    (net (code "48") (name "Net-(IC7A-I0)") (class "Default")
      (node (ref "IC7") (pin "1") (pinfunction "I0_1") (pintype "input"))
      (node (ref "IC8") (pin "4") (pinfunction "Y0_4") (pintype "output"))
    )
    (net (code "49") (name "Net-(IC7A-I1)") (class "Default")
      (node (ref "IC7") (pin "10") (pinfunction "I1_10") (pintype "input"))
      (node (ref "IC7") (pin "2") (pinfunction "I1_2") (pintype "input"))
      (node (ref "IC7") (pin "5") (pinfunction "I1_5") (pintype "input"))
      (node (ref "IC8") (pin "7") (pinfunction "Y3_7") (pintype "output"))
    )
    (net (code "50") (name "Net-(IC7B-I0)") (class "Default")
      (node (ref "IC7") (pin "4") (pinfunction "I0_4") (pintype "input"))
      (node (ref "IC8") (pin "5") (pinfunction "Y1_5") (pintype "output"))
    )
    (net (code "51") (name "Net-(IC7C-I0)") (class "Default")
      (node (ref "IC7") (pin "9") (pinfunction "I0_9") (pintype "input"))
      (node (ref "IC8") (pin "6") (pinfunction "Y2_6") (pintype "output"))
    )
    (net (code "52") (name "Net-(IC7D-O)") (class "Default")
      (node (ref "IC7") (pin "11") (pinfunction "O_11") (pintype "output"))
      (node (ref "IC8") (pin "1") (pinfunction "G_1") (pintype "input"))
    )
    (net (code "53") (name "Net-(IC13A-AREF)") (class "Default")
      (node (ref "C6") (pin "1") (pinfunction "1_1") (pintype "passive"))
      (node (ref "IC13") (pin "20") (pinfunction "AREF_20") (pintype "passive"))
    )
    (net (code "54") (name "Net-(IC13A-PB6(XTAL1{slash}TOSC1{slash}PCINT6))") (class "Default")
      (node (ref "C5") (pin "2") (pinfunction "2_2") (pintype "passive"))
      (node (ref "IC13") (pin "7") (pinfunction "PB6(XTAL1/TOSC1/PCINT6)_7") (pintype "bidirectional"))
      (node (ref "Q1") (pin "3") (pinfunction "2_3") (pintype "passive"))
    )
    (net (code "55") (name "Net-(IC13A-PB7(XTAL2{slash}TOSC2{slash}PCINT7))") (class "Default")
      (node (ref "C4") (pin "2") (pinfunction "2_2") (pintype "passive"))
      (node (ref "IC13") (pin "8") (pinfunction "PB7(XTAL2/TOSC2/PCINT7)_8") (pintype "bidirectional"))
      (node (ref "Q1") (pin "1") (pinfunction "1_1") (pintype "passive"))
    )
    (net (code "56") (name "Net-(LED_PWR-PadA)") (class "Default")
      (node (ref "LED_PWR") (pin "A") (pinfunction "A_A") (pintype "passive"))
      (node (ref "R5") (pin "1") (pinfunction "1_1") (pintype "passive"))
    )
    (net (code "57") (name "Net-(LED_RX-PadA)") (class "Default")
      (node (ref "LED_RX") (pin "A") (pinfunction "A_A") (pintype "passive"))
      (node (ref "R11") (pin "1") (pinfunction "1_1") (pintype "passive"))
    )
    (net (code "58") (name "Net-(LED_TX-PadA)") (class "Default")
      (node (ref "LED_TX") (pin "A") (pinfunction "A_A") (pintype "passive"))
      (node (ref "R10") (pin "1") (pinfunction "1_1") (pintype "passive"))
    )
    (net (code "59") (name "Net-(R13-Pad1)") (class "Default")
      (node (ref "R13") (pin "1") (pinfunction "1_1") (pintype "passive"))
      (node (ref "S1") (pin "12") (pinfunction "12_12") (pintype "passive"))
    )
    (net (code "60") (name "Net-(R14-Pad1)") (class "Default")
      (node (ref "R14") (pin "1") (pinfunction "1_1") (pintype "passive"))
      (node (ref "S1") (pin "11") (pinfunction "11_11") (pintype "passive"))
    )
    (net (code "61") (name "Net-(R15-Pad1)") (class "Default")
      (node (ref "R15") (pin "1") (pinfunction "1_1") (pintype "passive"))
      (node (ref "S1") (pin "10") (pinfunction "10_10") (pintype "passive"))
    )
    (net (code "62") (name "Net-(R16-Pad1)") (class "Default")
      (node (ref "R16") (pin "1") (pinfunction "1_1") (pintype "passive"))
      (node (ref "S1") (pin "9") (pinfunction "9_9") (pintype "passive"))
    )
    (net (code "63") (name "Net-(R18-Pad1)") (class "Default")
      (node (ref "R18") (pin "1") (pinfunction "1_1") (pintype "passive"))
      (node (ref "S1") (pin "8") (pinfunction "8_8") (pintype "passive"))
    )
    (net (code "64") (name "Net-(R19-Pad1)") (class "Default")
      (node (ref "R19") (pin "1") (pinfunction "1_1") (pintype "passive"))
      (node (ref "S1") (pin "7") (pinfunction "7_7") (pintype "passive"))
    )
    (net (code "65") (name "Net-(TRIGD-P)") (class "Default")
      (node (ref "R12") (pin "1") (pinfunction "1_1") (pintype "passive"))
      (node (ref "TRIG") (pin "4") (pinfunction "P_4") (pintype "passive"))
    )
    (net (code "66") (name "Net-(USB-VCC)") (class "Default")
      (node (ref "FS1") (pin "1") (pinfunction "1_1") (pintype "passive"))
      (node (ref "USB") (pin "1") (pinfunction "VCC_1") (pintype "bidirectional"))
    )
    (net (code "67") (name "RX") (class "Default")
      (node (ref "IC13") (pin "30") (pinfunction "PD0(RXD/PCINT16)_30") (pintype "bidirectional"))
      (node (ref "R8") (pin "2") (pinfunction "2_2") (pintype "passive"))
    )
    (net (code "68") (name "SCK") (class "Default")
      (node (ref "IC13") (pin "17") (pinfunction "PB5(SCK/PCINT5)_17") (pintype "bidirectional"))
      (node (ref "ISP1") (pin "3") (pinfunction "SCK_3") (pintype "passive"))
    )
    (net (code "69") (name "TX") (class "Default")
      (node (ref "IC13") (pin "31") (pinfunction "PD1(TXD/PCINT17)_31") (pintype "bidirectional"))
      (node (ref "R9") (pin "2") (pinfunction "2_2") (pintype "passive"))
    )
    (net (code "70") (name "unconnected-(IC1-P$4-Pad4)") (class "Default")
      (node (ref "IC1") (pin "4") (pinfunction "P$4_4") (pintype "bidirectional"))
    )
    (net (code "71") (name "unconnected-(IC1-P$6-Pad6)") (class "Default")
      (node (ref "IC1") (pin "6") (pinfunction "P$6_6") (pintype "bidirectional"))
    )
    (net (code "72") (name "unconnected-(IC4A-RO-Pad2)") (class "Default")
      (node (ref "IC4") (pin "2") (pinfunction "RO_2") (pintype "output"))
    )
    (net (code "73") (name "unconnected-(IC6-CBUS2-Pad13)") (class "Default")
      (node (ref "IC6") (pin "13") (pinfunction "CBUS2_13") (pintype "bidirectional"))
    )
    (net (code "74") (name "unconnected-(IC6-CBUS3-Pad14)") (class "Default")
      (node (ref "IC6") (pin "14") (pinfunction "CBUS3_14") (pintype "bidirectional"))
    )
    (net (code "75") (name "unconnected-(IC6-CBUS4-Pad12)") (class "Default")
      (node (ref "IC6") (pin "12") (pinfunction "CBUS4_12") (pintype "bidirectional"))
    )
    (net (code "76") (name "unconnected-(IC6-OSCI-Pad27)") (class "Default")
      (node (ref "IC6") (pin "27") (pinfunction "OSCI_27") (pintype "input"))
    )
    (net (code "77") (name "unconnected-(IC6-OSCO-Pad28)") (class "Default")
      (node (ref "IC6") (pin "28") (pinfunction "OSCO_28") (pintype "output"))
    )
    (net (code "78") (name "unconnected-(IC6-~{CTS}-Pad11)") (class "Default")
      (node (ref "IC6") (pin "11") (pinfunction "~{CTS}_11") (pintype "input"))
    )
    (net (code "79") (name "unconnected-(IC6-~{DCD}-Pad10)") (class "Default")
      (node (ref "IC6") (pin "10") (pinfunction "~{DCD}_10") (pintype "input"))
    )
    (net (code "80") (name "unconnected-(IC6-~{DSR}-Pad9)") (class "Default")
      (node (ref "IC6") (pin "9") (pinfunction "~{DSR}_9") (pintype "input"))
    )
    (net (code "81") (name "unconnected-(IC6-~{RI}-Pad6)") (class "Default")
      (node (ref "IC6") (pin "6") (pinfunction "~{RI}_6") (pintype "input"))
    )
    (net (code "82") (name "unconnected-(IC6-~{RTS}-Pad3)") (class "Default")
      (node (ref "IC6") (pin "3") (pinfunction "~{RTS}_3") (pintype "output"))
    )
    (net (code "83") (name "unconnected-(IC8B-Y0-Pad12)") (class "Default")
      (node (ref "IC8") (pin "12") (pinfunction "Y0_12") (pintype "output"))
    )
    (net (code "84") (name "unconnected-(IC8B-Y1-Pad11)") (class "Default")
      (node (ref "IC8") (pin "11") (pinfunction "Y1_11") (pintype "output"))
    )
    (net (code "85") (name "unconnected-(IC8B-Y2-Pad10)") (class "Default")
      (node (ref "IC8") (pin "10") (pinfunction "Y2_10") (pintype "output"))
    )
    (net (code "86") (name "unconnected-(IC8B-Y3-Pad9)") (class "Default")
      (node (ref "IC8") (pin "9") (pinfunction "Y3_9") (pintype "output"))
    )
    (net (code "87") (name "unconnected-(IC9A-RO-Pad2)") (class "Default")
      (node (ref "IC9") (pin "2") (pinfunction "RO_2") (pintype "output"))
    )
    (net (code "88") (name "unconnected-(IC10A-RO-Pad2)") (class "Default")
      (node (ref "IC10") (pin "2") (pinfunction "RO_2") (pintype "output"))
    )
    (net (code "89") (name "unconnected-(IC12-P$6-Pad6)") (class "Default")
      (node (ref "IC12") (pin "6") (pinfunction "P$6_6") (pintype "bidirectional"))
    )
    (net (code "90") (name "unconnected-(IC13A-ADC6-Pad19)") (class "Default")
      (node (ref "IC13") (pin "19") (pinfunction "ADC6_19") (pintype "passive"))
    )
    (net (code "91") (name "unconnected-(IC13A-ADC7-Pad22)") (class "Default")
      (node (ref "IC13") (pin "22") (pinfunction "ADC7_22") (pintype "passive"))
    )
    (net (code "92") (name "unconnected-(IC13A-PB0(ICP1{slash}CLKO{slash}PCINT0)-Pad12)") (class "Default")
      (node (ref "IC13") (pin "12") (pinfunction "PB0(ICP1/CLKO/PCINT0)_12") (pintype "bidirectional"))
    )
    (net (code "93") (name "unconnected-(IC13A-PC4(ADC4{slash}SDA{slash}PCINT12)-Pad27)") (class "Default")
      (node (ref "IC13") (pin "27") (pinfunction "PC4(ADC4/SDA/PCINT12)_27") (pintype "bidirectional"))
    )
    (net (code "94") (name "unconnected-(IC13A-PD5(T1{slash}OC0B{slash}PCINT21)-Pad9)") (class "Default")
      (node (ref "IC13") (pin "9") (pinfunction "PD5(T1/OC0B/PCINT21)_9") (pintype "bidirectional"))
    )
    (net (code "95") (name "unconnected-(IC13A-PD6(AIN0{slash}OC0A{slash}PCINT22)-Pad10)") (class "Default")
      (node (ref "IC13") (pin "10") (pinfunction "PD6(AIN0/OC0A/PCINT22)_10") (pintype "bidirectional"))
    )
    (net (code "96") (name "~{RST}") (class "Default")
      (node (ref "C15") (pin "1") (pinfunction "1_1") (pintype "passive"))
      (node (ref "IC13") (pin "29") (pinfunction "PC6(~{RESET}/PCINT14)_29") (pintype "bidirectional"))
      (node (ref "ISP1") (pin "5") (pinfunction "RST_5") (pintype "passive"))
      (node (ref "R4") (pin "1") (pinfunction "1_1") (pintype "passive"))
    )
  )
)
